# Ethernet.net
KiCad netlist of a schematic drawn in Altium Designer
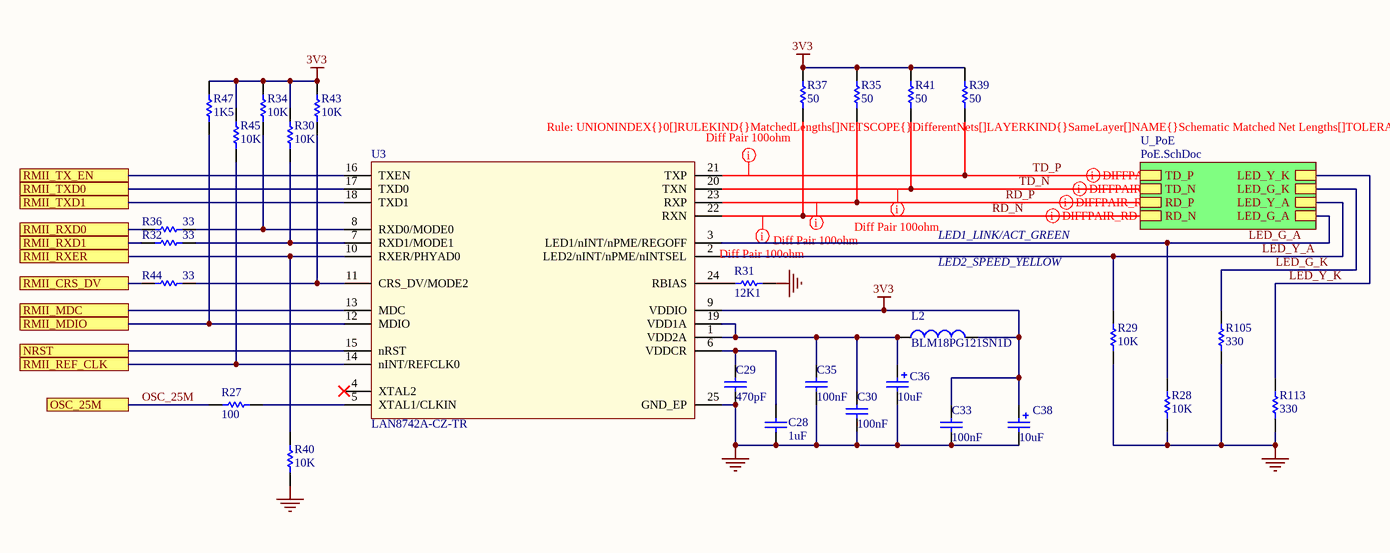
[diagram p0: Ethernet.SchDoc]

(export (version "E")
  (design (tool "Eeschema 10.0.6"))
  (components
    (comp (ref "C28")
      (value "1uF")
      (footprint "0603C")
      (description "Capacitor,1uF,16V,X5R,10%,0603,YAGEO")
      (libsource (lib "MCD_TOOLS") (part "Cap_1uF_X5R_10%_0603"))
    )
    (comp (ref "C29")
      (value "470pF")
      (footprint "0402C")
      (description "Capacitor,470pF,16V,X7R,10%,0402,YAGEO")
      (libsource (lib "MCD_TOOLS") (part "Cap_470pF_X7R_10%_0402"))
    )
    (comp (ref "C30")
      (value "100nF")
      (footprint "0402C")
      (description "Capacitor,100nF,16V,X7R,10%,0402,YAGEO")
      (libsource (lib "MCD_TOOLS") (part "Cap_100nF_X7R_10%_0402"))
    )
    (comp (ref "C33")
      (value "100nF")
      (footprint "0402C")
      (description "Capacitor,100nF,16V,X7R,10%,0402,YAGEO")
      (libsource (lib "MCD_TOOLS") (part "Cap_100nF_X7R_10%_0402"))
    )
    (comp (ref "C35")
      (value "100nF")
      (footprint "0402C")
      (description "Capacitor,100nF,16V,X7R,10%,0402,YAGEO")
      (libsource (lib "MCD_TOOLS") (part "Cap_100nF_X7R_10%_0402"))
    )
    (comp (ref "C36")
      (value "10uF")
      (footprint "TAN-A")
      (description "Polarized Capacitor,10uF,10V,10%,typeA,VISHAY")
      (libsource (lib "MCD_TOOLS") (part "Cap_10uF_POL_10%_TANA"))
    )
    (comp (ref "C38")
      (value "10uF")
      (footprint "TAN-A")
      (description "Polarized Capacitor,10uF,10V,10%,typeA,VISHAY")
      (libsource (lib "MCD_TOOLS") (part "Cap_10uF_POL_10%_TANA"))
    )
    (comp (ref "L2")
      (value "BLM18PG121SN1D")
      (footprint "0603L")
      (description "Bead,120R,2A,0603,BLM18PG121SN1D,MURATA")
      (libsource (lib "MCD_TOOLS") (part "BEAD_120R_2A_0603"))
    )
    (comp (ref "R27")
      (value "100")
      (footprint "0402R")
      (description "Resistor,100,0402,1%,YAGEO")
      (libsource (lib "MCD_TOOLS") (part "Res_100_1%_0402"))
    )
    (comp (ref "R28")
      (value "10K")
      (footprint "0402R")
      (description "Resistor,10K,0402,1%,YAGEO")
      (libsource (lib "MCD_TOOLS") (part "Res_10K_1%_0402"))
    )
    (comp (ref "R29")
      (value "10K")
      (footprint "0402R")
      (description "Resistor,10K,0402,1%,YAGEO")
      (libsource (lib "MCD_TOOLS") (part "Res_10K_1%_0402"))
    )
    (comp (ref "R30")
      (value "10K")
      (footprint "0402R")
      (description "Resistor,10K,0402,1%,YAGEO")
      (libsource (lib "MCD_TOOLS_RESISTOR") (part "Res_10K_1%_0402"))
    )
    (comp (ref "R31")
      (value "12K1")
      (footprint "0603R")
      (description "Resistor,12K1,0603,1%,VISHAY")
      (libsource (lib "MCD_TOOLS") (part "Res_12K1_1%_0603"))
    )
    (comp (ref "R32")
      (value "33")
      (footprint "0402R")
      (description "Resistor,33,0402,1%,YAGEO")
      (libsource (lib "MCD_TOOLS") (part "Res_33_1%_0402"))
    )
    (comp (ref "R34")
      (value "10K")
      (footprint "0402R")
      (description "Resistor,10K,0402,1%,YAGEO")
      (libsource (lib "MCD_TOOLS_RESISTOR") (part "Res_10K_1%_0402"))
    )
    (comp (ref "R35")
      (value "50")
      (footprint "0402R")
      (description "Resistor,50,0402,1%,YAGEO")
      (libsource (lib "MCD_TOOLS") (part "Res_50_1%_0402"))
    )
    (comp (ref "R36")
      (value "33")
      (footprint "0402R")
      (description "Resistor,33,0402,1%,YAGEO")
      (libsource (lib "MCD_TOOLS") (part "Res_33_1%_0402"))
    )
    (comp (ref "R37")
      (value "50")
      (footprint "0402R")
      (description "Resistor,50,0402,1%,YAGEO")
      (libsource (lib "MCD_TOOLS") (part "Res_50_1%_0402"))
    )
    (comp (ref "R39")
      (value "50")
      (footprint "0402R")
      (description "Resistor,50,0402,1%,YAGEO")
      (libsource (lib "MCD_TOOLS") (part "Res_50_1%_0402"))
    )
    (comp (ref "R40")
      (value "10K")
      (footprint "0402R")
      (description "Resistor,10K,0402,1%,YAGEO")
      (libsource (lib "MCD_TOOLS_RESISTOR") (part "Res_10K_1%_0402"))
    )
    (comp (ref "R41")
      (value "50")
      (footprint "0402R")
      (description "Resistor,50,0402,1%,YAGEO")
      (libsource (lib "MCD_TOOLS") (part "Res_50_1%_0402"))
    )
    (comp (ref "R43")
      (value "10K")
      (footprint "0402R")
      (description "Resistor,10K,0402,1%,YAGEO")
      (libsource (lib "MCD_TOOLS_RESISTOR") (part "Res_10K_1%_0402"))
    )
    (comp (ref "R44")
      (value "33")
      (footprint "0402R")
      (description "Resistor,33,0402,1%,YAGEO")
      (libsource (lib "MCD_TOOLS") (part "Res_33_1%_0402"))
    )
    (comp (ref "R45")
      (value "10K")
      (footprint "0402R")
      (description "Resistor,10K,0402,1%,YAGEO")
      (libsource (lib "MCD_TOOLS_RESISTOR") (part "Res_10K_1%_0402"))
    )
    (comp (ref "R47")
      (value "1K5")
      (footprint "0402R")
      (description "Resistor,1K5,0402,1%,YAGEO")
      (libsource (lib "MCD_TOOLS") (part "Res_1K5_1%_0402"))
    )
    (comp (ref "R105")
      (value "330")
      (footprint "0402R")
      (description "Resistor,330,0402,1%,YAGEO")
      (libsource (lib "MCD_TOOLS") (part "Res_330_1%_0402"))
    )
    (comp (ref "R113")
      (value "330")
      (footprint "0402R")
      (description "Resistor,330,0402,1%,YAGEO")
      (libsource (lib "MCD_TOOLS") (part "Res_330_1%_0402"))
    )
    (comp (ref "U3")
      (value "LAN8742A-CZ-TR")
      (footprint "QFN24_0R5_4X4")
      (fields (field (name "PROVIDED") "Sub Co"))
      (libsource (lib "MCD_TOOLS_MISCELLANEOUS") (part "LAN8742A-CZ-TR"))
    )
  )
  (nets
    (net (code "1") (name "/LED_G_A") (class "Default")
      (node (ref "R28") (pin "2") (pinfunction "2_2") (pintype "passive"))
      (node (ref "U3") (pin "3") (pinfunction "LED1/nINT/nPME/REGOFF_3") (pintype "passive"))
    )
    (net (code "2") (name "/LED_G_K") (class "Default")
      (node (ref "R105") (pin "2") (pinfunction "2_2") (pintype "passive"))
    )
    (net (code "3") (name "/LED_Y_A") (class "Default")
      (node (ref "R29") (pin "2") (pinfunction "2_2") (pintype "passive"))
      (node (ref "U3") (pin "2") (pinfunction "LED2/nINT/nPME/nINTSEL_2") (pintype "passive"))
    )
    (net (code "4") (name "/LED_Y_K") (class "Default")
      (node (ref "R113") (pin "2") (pinfunction "2_2") (pintype "passive"))
    )
    (net (code "5") (name "/NRST") (class "Default")
      (node (ref "U3") (pin "15") (pinfunction "nRST_15") (pintype "passive"))
    )
    (net (code "6") (name "/OSC_25M") (class "Default")
      (node (ref "R27") (pin "1") (pinfunction "1_1") (pintype "passive"))
    )
    (net (code "7") (name "/RD_N") (class "Default")
      (node (ref "R37") (pin "2") (pinfunction "2_2") (pintype "passive"))
      (node (ref "U3") (pin "22") (pinfunction "RXN_22") (pintype "passive"))
    )
    (net (code "8") (name "/RD_P") (class "Default")
      (node (ref "R35") (pin "2") (pinfunction "2_2") (pintype "passive"))
      (node (ref "U3") (pin "23") (pinfunction "RXP_23") (pintype "passive"))
    )
    (net (code "9") (name "/RMII_CRS_DV") (class "Default")
      (node (ref "R44") (pin "2") (pinfunction "2_2") (pintype "passive"))
    )
    (net (code "10") (name "/RMII_MDC") (class "Default")
      (node (ref "U3") (pin "13") (pinfunction "MDC_13") (pintype "passive"))
    )
    (net (code "11") (name "/RMII_MDIO") (class "Default")
      (node (ref "R47") (pin "1") (pinfunction "1_1") (pintype "passive"))
      (node (ref "U3") (pin "12") (pinfunction "MDIO_12") (pintype "passive"))
    )
    (net (code "12") (name "/RMII_REF_CLK") (class "Default")
      (node (ref "R45") (pin "1") (pinfunction "1_1") (pintype "passive"))
      (node (ref "U3") (pin "14") (pinfunction "nINT/REFCLK0_14") (pintype "passive"))
    )
    (net (code "13") (name "/RMII_RXD0") (class "Default")
      (node (ref "R36") (pin "2") (pinfunction "2_2") (pintype "passive"))
    )
    (net (code "14") (name "/RMII_RXD1") (class "Default")
      (node (ref "R32") (pin "2") (pinfunction "2_2") (pintype "passive"))
    )
    (net (code "15") (name "/RMII_RXER") (class "Default")
      (node (ref "R40") (pin "2") (pinfunction "2_2") (pintype "passive"))
      (node (ref "U3") (pin "10") (pinfunction "RXER/PHYAD0_10") (pintype "passive"))
    )
    (net (code "16") (name "/RMII_TXD0") (class "Default")
      (node (ref "U3") (pin "17") (pinfunction "TXD0_17") (pintype "passive"))
    )
    (net (code "17") (name "/RMII_TXD1") (class "Default")
      (node (ref "U3") (pin "18") (pinfunction "TXD1_18") (pintype "passive"))
    )
    (net (code "18") (name "/RMII_TX_EN") (class "Default")
      (node (ref "U3") (pin "16") (pinfunction "TXEN_16") (pintype "passive"))
    )
    (net (code "19") (name "/TD_N") (class "Default")
      (node (ref "R41") (pin "2") (pinfunction "2_2") (pintype "passive"))
      (node (ref "U3") (pin "20") (pinfunction "TXN_20") (pintype "passive"))
    )
    (net (code "20") (name "/TD_P") (class "Default")
      (node (ref "R39") (pin "2") (pinfunction "2_2") (pintype "passive"))
      (node (ref "U3") (pin "21") (pinfunction "TXP_21") (pintype "passive"))
    )
    (net (code "21") (name "3V3") (class "Default")
      (node (ref "C33") (pin "2") (pinfunction "2_2") (pintype "passive"))
      (node (ref "C38") (pin "1") (pinfunction "1_1") (pintype "passive"))
      (node (ref "L2") (pin "2") (pinfunction "2_2") (pintype "passive"))
      (node (ref "R30") (pin "2") (pinfunction "2_2") (pintype "passive"))
      (node (ref "R34") (pin "2") (pinfunction "2_2") (pintype "passive"))
      (node (ref "R35") (pin "1") (pinfunction "1_1") (pintype "passive"))
      (node (ref "R37") (pin "1") (pinfunction "1_1") (pintype "passive"))
      (node (ref "R39") (pin "1") (pinfunction "1_1") (pintype "passive"))
      (node (ref "R41") (pin "1") (pinfunction "1_1") (pintype "passive"))
      (node (ref "R43") (pin "2") (pinfunction "2_2") (pintype "passive"))
      (node (ref "R45") (pin "2") (pinfunction "2_2") (pintype "passive"))
      (node (ref "R47") (pin "2") (pinfunction "2_2") (pintype "passive"))
      (node (ref "U3") (pin "9") (pinfunction "VDDIO_9") (pintype "passive"))
    )
    (net (code "22") (name "GND") (class "Default")
      (node (ref "C28") (pin "1") (pinfunction "1_1") (pintype "passive"))
      (node (ref "C29") (pin "1") (pinfunction "1_1") (pintype "passive"))
      (node (ref "C30") (pin "1") (pinfunction "1_1") (pintype "passive"))
      (node (ref "C33") (pin "1") (pinfunction "1_1") (pintype "passive"))
      (node (ref "C35") (pin "1") (pinfunction "1_1") (pintype "passive"))
      (node (ref "C36") (pin "2") (pinfunction "2_2") (pintype "passive"))
      (node (ref "C38") (pin "2") (pinfunction "2_2") (pintype "passive"))
      (node (ref "R105") (pin "1") (pinfunction "1_1") (pintype "passive"))
      (node (ref "R113") (pin "1") (pinfunction "1_1") (pintype "passive"))
      (node (ref "R28") (pin "1") (pinfunction "1_1") (pintype "passive"))
      (node (ref "R29") (pin "1") (pinfunction "1_1") (pintype "passive"))
      (node (ref "R31") (pin "2") (pinfunction "2_2") (pintype "passive"))
      (node (ref "R40") (pin "1") (pinfunction "1_1") (pintype "passive"))
      (node (ref "U3") (pin "25") (pinfunction "GND_EP_25") (pintype "passive"))
    )
    (net (code "23") (name "Net-(U3-CRS_DV{slash}MODE2)") (class "Default")
      (node (ref "R43") (pin "1") (pinfunction "1_1") (pintype "passive"))
      (node (ref "R44") (pin "1") (pinfunction "1_1") (pintype "passive"))
      (node (ref "U3") (pin "11") (pinfunction "CRS_DV/MODE2_11") (pintype "passive"))
    )
    (net (code "24") (name "Net-(U3-RBIAS)") (class "Default")
      (node (ref "R31") (pin "1") (pinfunction "1_1") (pintype "passive"))
      (node (ref "U3") (pin "24") (pinfunction "RBIAS_24") (pintype "passive"))
    )
    (net (code "25") (name "Net-(U3-RXD0{slash}MODE0)") (class "Default")
      (node (ref "R34") (pin "1") (pinfunction "1_1") (pintype "passive"))
      (node (ref "R36") (pin "1") (pinfunction "1_1") (pintype "passive"))
      (node (ref "U3") (pin "8") (pinfunction "RXD0/MODE0_8") (pintype "passive"))
    )
    (net (code "26") (name "Net-(U3-RXD1{slash}MODE1)") (class "Default")
      (node (ref "R30") (pin "1") (pinfunction "1_1") (pintype "passive"))
      (node (ref "R32") (pin "1") (pinfunction "1_1") (pintype "passive"))
      (node (ref "U3") (pin "7") (pinfunction "RXD1/MODE1_7") (pintype "passive"))
    )
    (net (code "27") (name "Net-(U3-VDD1A)") (class "Default")
      (node (ref "C30") (pin "2") (pinfunction "2_2") (pintype "passive"))
      (node (ref "C35") (pin "2") (pinfunction "2_2") (pintype "passive"))
      (node (ref "C36") (pin "1") (pinfunction "1_1") (pintype "passive"))
      (node (ref "L2") (pin "1") (pinfunction "1_1") (pintype "passive"))
      (node (ref "U3") (pin "1") (pinfunction "VDD2A_1") (pintype "passive"))
      (node (ref "U3") (pin "19") (pinfunction "VDD1A_19") (pintype "passive"))
    )
    (net (code "28") (name "Net-(U3-VDDCR)") (class "Default")
      (node (ref "C28") (pin "2") (pinfunction "2_2") (pintype "passive"))
      (node (ref "C29") (pin "2") (pinfunction "2_2") (pintype "passive"))
      (node (ref "U3") (pin "6") (pinfunction "VDDCR_6") (pintype "passive"))
    )
    (net (code "29") (name "Net-(U3-XTAL1{slash}CLKIN)") (class "Default")
      (node (ref "R27") (pin "2") (pinfunction "2_2") (pintype "passive"))
      (node (ref "U3") (pin "5") (pinfunction "XTAL1/CLKIN_5") (pintype "passive"))
    )
    (net (code "30") (name "unconnected-(U3-XTAL2-Pad4)") (class "Default")
      (node (ref "U3") (pin "4") (pinfunction "XTAL2_4") (pintype "passive+no_connect"))
    )
  )
)
